# KMO_IO_MV2_3.net
KiCad netlist of a schematic drawn in EAGLE
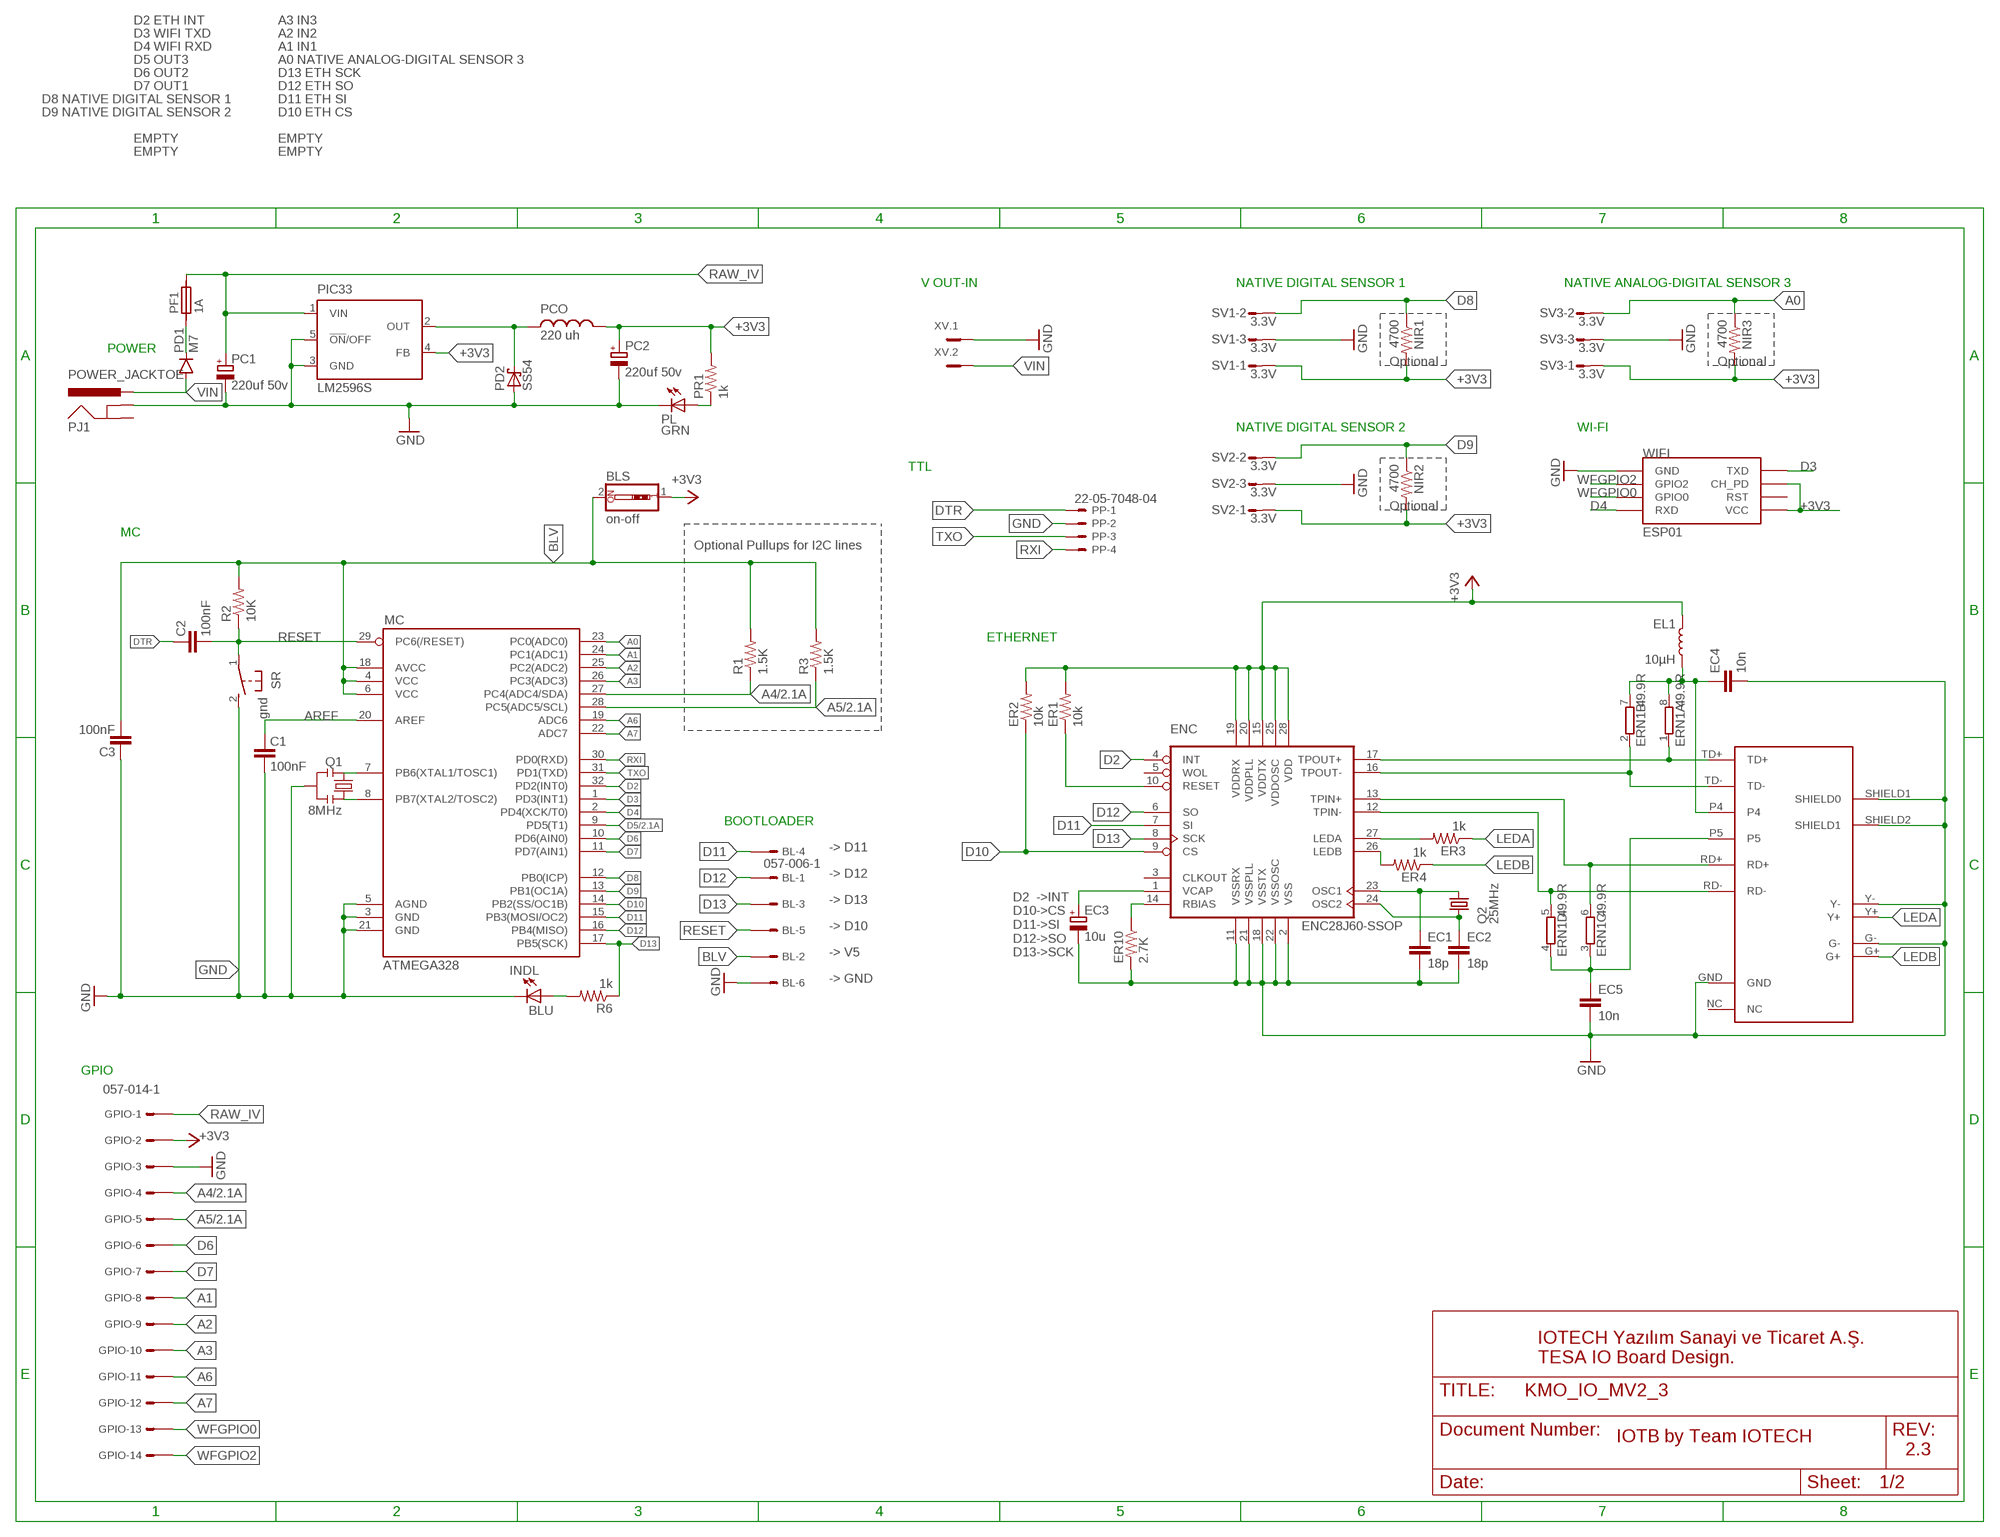
[diagram p0: schematic, sheet 1]
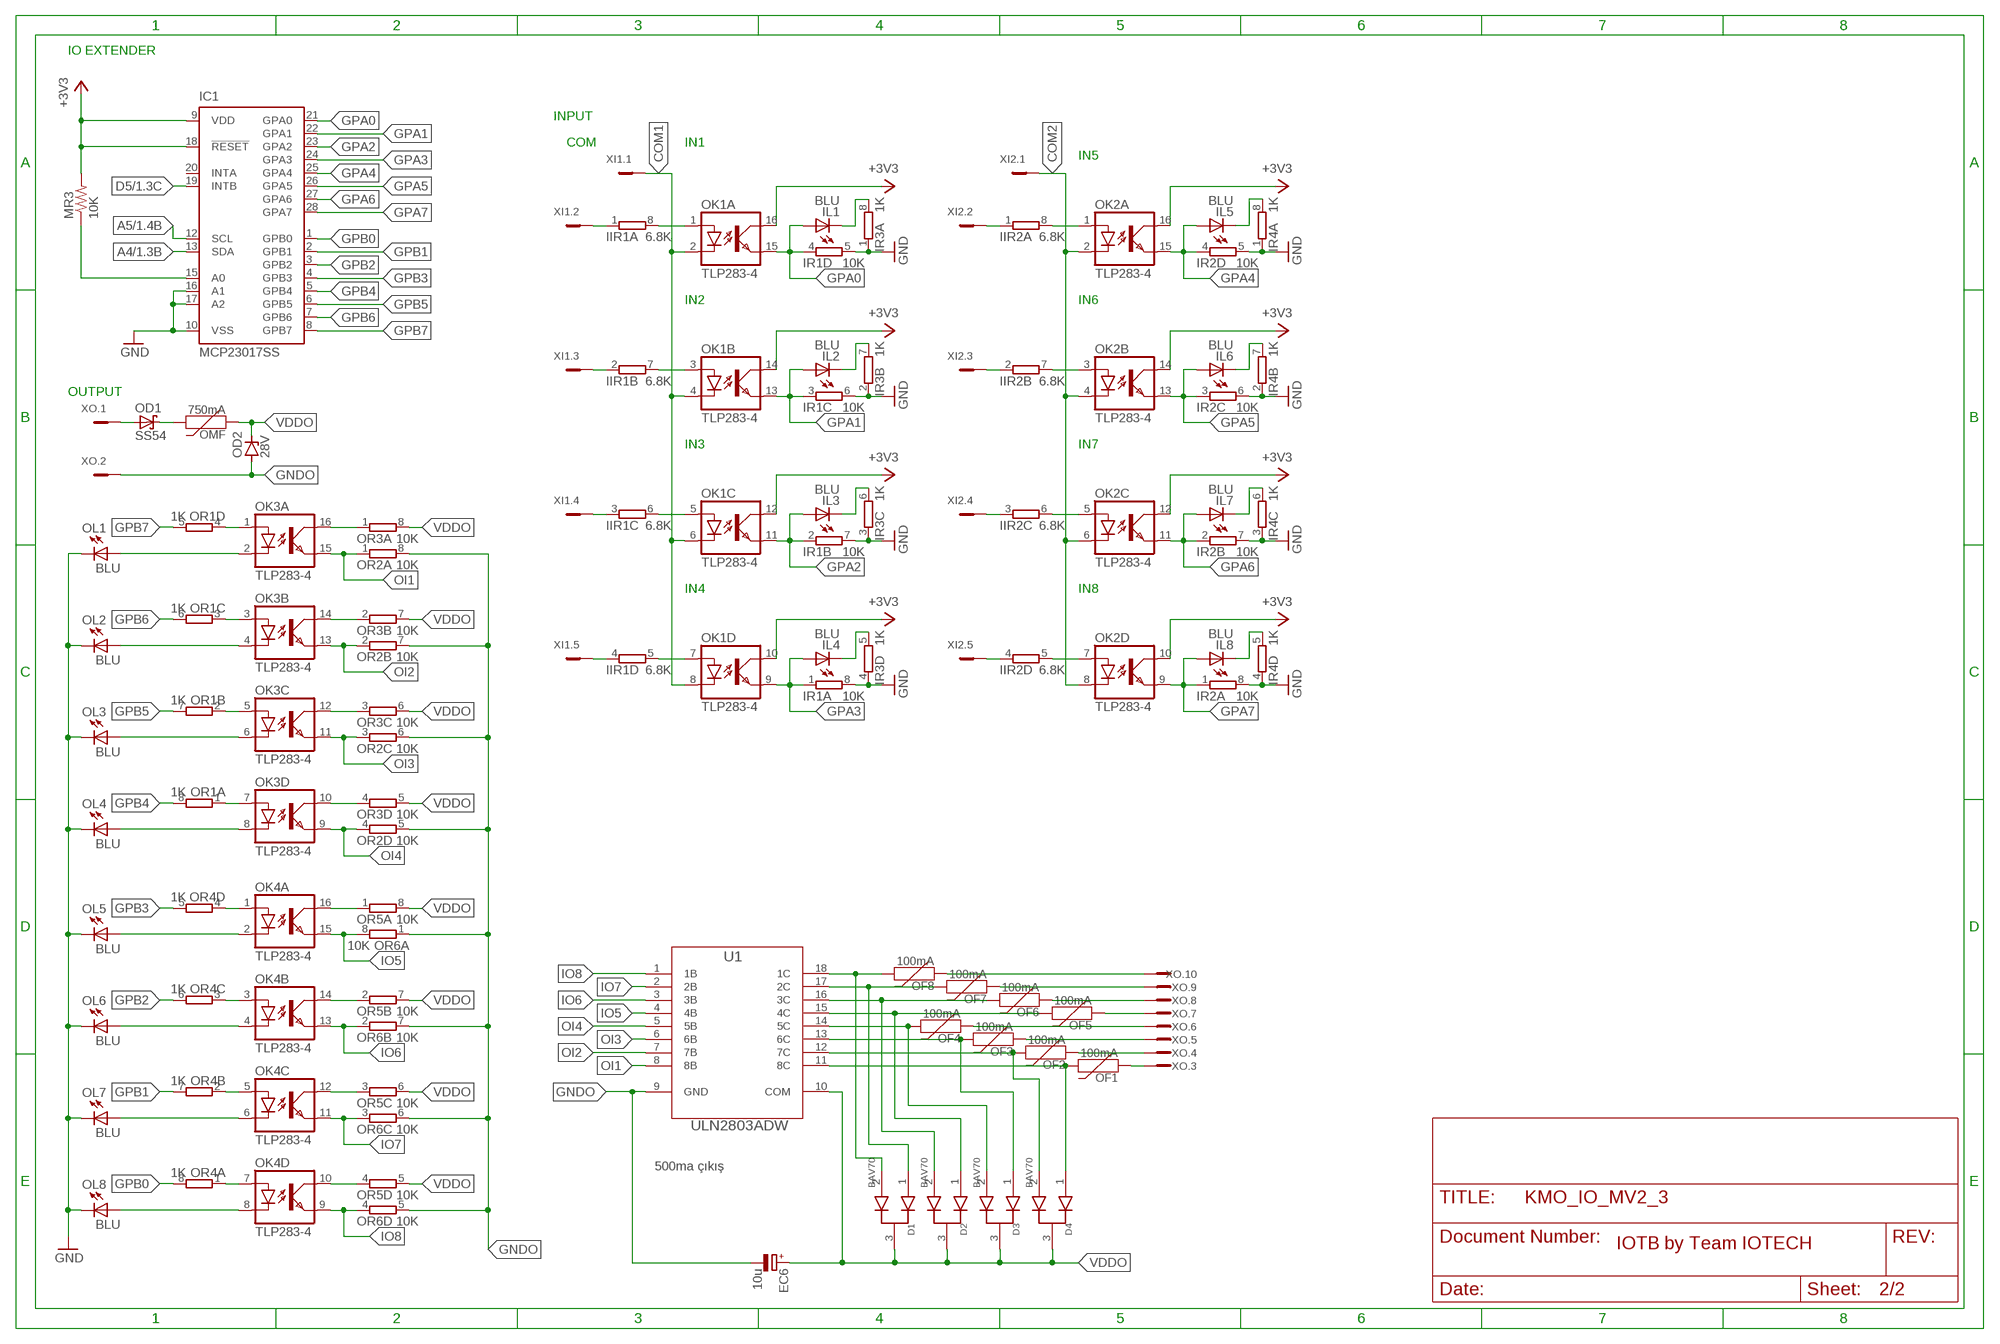
[diagram p1: schematic, sheet 2]

(export (version "E")
  (design (tool "Eeschema 10.0.6"))
  (components
    (comp (ref "D1")
      (value "BAV70")
      (footprint "eagle-import:SOT-23-3")
      (fields (field (name "MF") "Multicomp") (field (name "MP") "BAV70+"))
      (libsource (lib "eagle-import") (part "BAV70"))
    )
    (comp (ref "D2")
      (value "BAV70")
      (footprint "eagle-import:SOT-23-3")
      (fields (field (name "MF") "Multicomp") (field (name "MP") "BAV70+"))
      (libsource (lib "eagle-import") (part "BAV70"))
    )
    (comp (ref "D3")
      (value "BAV70")
      (footprint "eagle-import:SOT-23-3")
      (fields (field (name "MF") "Multicomp") (field (name "MP") "BAV70+"))
      (libsource (lib "eagle-import") (part "BAV70"))
    )
    (comp (ref "D4")
      (value "BAV70")
      (footprint "eagle-import:SOT-23-3")
      (fields (field (name "MF") "Multicomp") (field (name "MP") "BAV70+"))
      (libsource (lib "eagle-import") (part "BAV70"))
    )
    (comp (ref "EC6")
      (value "10u")
      (footprint "eagle-import:CT3216")
      (libsource (lib "eagle-import") (part "CPOL-EUCT3216"))
    )
    (comp (ref "IC1")
      (value "MCP23017SS")
      (footprint "eagle-import:SSOP28")
      (fields (field (name "MF") "MICROCHIP") (field (name "MPN") "MCP23017-E/SS"))
      (libsource (lib "eagle-import") (part "MCP23017SS"))
    )
    (comp (ref "IIR1")
      (value "6.8K")
      (footprint "eagle-import:0603-ARV")
      (libsource (lib "eagle-import") (part "4R-N0603-ARV"))
    )
    (comp (ref "IIR2")
      (value "6.8K")
      (footprint "eagle-import:0603-ARV")
      (libsource (lib "eagle-import") (part "4R-N0603-ARV"))
    )
    (comp (ref "IL1")
      (value "BLU")
      (footprint "eagle-import:CHIP-LED0805")
      (libsource (lib "eagle-import") (part "LEDCHIP-LED0805"))
    )
    (comp (ref "IL2")
      (value "BLU")
      (footprint "eagle-import:CHIP-LED0805")
      (libsource (lib "eagle-import") (part "LEDCHIP-LED0805"))
    )
    (comp (ref "IL3")
      (value "BLU")
      (footprint "eagle-import:CHIP-LED0805")
      (libsource (lib "eagle-import") (part "LEDCHIP-LED0805"))
    )
    (comp (ref "IL4")
      (value "BLU")
      (footprint "eagle-import:CHIP-LED0805")
      (libsource (lib "eagle-import") (part "LEDCHIP-LED0805"))
    )
    (comp (ref "IL5")
      (value "BLU")
      (footprint "eagle-import:CHIP-LED0805")
      (libsource (lib "eagle-import") (part "LEDCHIP-LED0805"))
    )
    (comp (ref "IL6")
      (value "BLU")
      (footprint "eagle-import:CHIP-LED0805")
      (libsource (lib "eagle-import") (part "LEDCHIP-LED0805"))
    )
    (comp (ref "IL7")
      (value "BLU")
      (footprint "eagle-import:CHIP-LED0805")
      (libsource (lib "eagle-import") (part "LEDCHIP-LED0805"))
    )
    (comp (ref "IL8")
      (value "BLU")
      (footprint "eagle-import:CHIP-LED0805")
      (libsource (lib "eagle-import") (part "LEDCHIP-LED0805"))
    )
    (comp (ref "IR1")
      (value "10K")
      (footprint "eagle-import:0603-ARV")
      (libsource (lib "eagle-import") (part "4R-N0603-ARV"))
    )
    (comp (ref "IR2")
      (value "10K")
      (footprint "eagle-import:0603-ARV")
      (libsource (lib "eagle-import") (part "4R-N0603-ARV"))
    )
    (comp (ref "IR3")
      (value "1K")
      (footprint "eagle-import:0603-ARV")
      (libsource (lib "eagle-import") (part "4R-N0603-ARV"))
    )
    (comp (ref "IR4")
      (value "1K")
      (footprint "eagle-import:0603-ARV")
      (libsource (lib "eagle-import") (part "4R-N0603-ARV"))
    )
    (comp (ref "MR3")
      (value "10K")
      (footprint "eagle-import:0805")
      (libsource (lib "eagle-import") (part "RESISTOR0805-RES"))
    )
    (comp (ref "OD1")
      (value "SS54")
      (footprint "eagle-import:SMB")
      (libsource (lib "eagle-import") (part "SCHOTTKY-DIODESMD"))
    )
    (comp (ref "OD2")
      (value "28V")
      (footprint "eagle-import:SMB")
      (libsource (lib "eagle-import") (part "ZENER-DIODESMB"))
    )
    (comp (ref "OF1")
      (value "100mA")
      (footprint "eagle-import:1206")
      (libsource (lib "eagle-import") (part "PPTC_0.75A"))
    )
    (comp (ref "OF2")
      (value "100mA")
      (footprint "eagle-import:1206")
      (libsource (lib "eagle-import") (part "PPTC_0.75A"))
    )
    (comp (ref "OF3")
      (value "100mA")
      (footprint "eagle-import:1206")
      (libsource (lib "eagle-import") (part "PPTC_0.75A"))
    )
    (comp (ref "OF4")
      (value "100mA")
      (footprint "eagle-import:1206")
      (libsource (lib "eagle-import") (part "PPTC_0.75A"))
    )
    (comp (ref "OF5")
      (value "100mA")
      (footprint "eagle-import:1206")
      (libsource (lib "eagle-import") (part "PPTC_0.75A"))
    )
    (comp (ref "OF6")
      (value "100mA")
      (footprint "eagle-import:1206")
      (libsource (lib "eagle-import") (part "PPTC_0.75A"))
    )
    (comp (ref "OF7")
      (value "100mA")
      (footprint "eagle-import:1206")
      (libsource (lib "eagle-import") (part "PPTC_0.75A"))
    )
    (comp (ref "OF8")
      (value "100mA")
      (footprint "eagle-import:1206")
      (libsource (lib "eagle-import") (part "PPTC_0.75A"))
    )
    (comp (ref "OK1")
      (value "TLP283-4")
      (footprint "eagle-import:MINI-FLAT-16")
      (fields (field (name "SPICEPREFIX") "O"))
      (libsource (lib "eagle-import") (part "TLP283-4"))
    )
    (comp (ref "OK2")
      (value "TLP283-4")
      (footprint "eagle-import:MINI-FLAT-16")
      (fields (field (name "SPICEPREFIX") "O"))
      (libsource (lib "eagle-import") (part "TLP283-4"))
    )
    (comp (ref "OK3")
      (value "TLP283-4")
      (footprint "eagle-import:MINI-FLAT-16")
      (libsource (lib "eagle-import") (part "TLP283-4"))
    )
    (comp (ref "OK4")
      (value "TLP283-4")
      (footprint "eagle-import:MINI-FLAT-16")
      (libsource (lib "eagle-import") (part "TLP283-4"))
    )
    (comp (ref "OL1")
      (value "BLU")
      (footprint "eagle-import:CHIP-LED0805")
      (libsource (lib "eagle-import") (part "LEDCHIP-LED0805"))
    )
    (comp (ref "OL2")
      (value "BLU")
      (footprint "eagle-import:CHIP-LED0805")
      (libsource (lib "eagle-import") (part "LEDCHIP-LED0805"))
    )
    (comp (ref "OL3")
      (value "BLU")
      (footprint "eagle-import:CHIP-LED0805")
      (libsource (lib "eagle-import") (part "LEDCHIP-LED0805"))
    )
    (comp (ref "OL4")
      (value "BLU")
      (footprint "eagle-import:CHIP-LED0805")
      (libsource (lib "eagle-import") (part "LEDCHIP-LED0805"))
    )
    (comp (ref "OL5")
      (value "BLU")
      (footprint "eagle-import:CHIP-LED0805")
      (libsource (lib "eagle-import") (part "LEDCHIP-LED0805"))
    )
    (comp (ref "OL6")
      (value "BLU")
      (footprint "eagle-import:CHIP-LED0805")
      (libsource (lib "eagle-import") (part "LEDCHIP-LED0805"))
    )
    (comp (ref "OL7")
      (value "BLU")
      (footprint "eagle-import:CHIP-LED0805")
      (libsource (lib "eagle-import") (part "LEDCHIP-LED0805"))
    )
    (comp (ref "OL8")
      (value "BLU")
      (footprint "eagle-import:CHIP-LED0805")
      (libsource (lib "eagle-import") (part "LEDCHIP-LED0805"))
    )
    (comp (ref "OMF")
      (value "750mA")
      (footprint "eagle-import:1206")
      (libsource (lib "eagle-import") (part "PPTC_0.75A"))
    )
    (comp (ref "OR1")
      (value "1K")
      (footprint "eagle-import:0603-ARV")
      (libsource (lib "eagle-import") (part "4R-N0603-ARV"))
    )
    (comp (ref "OR2")
      (value "10K")
      (footprint "eagle-import:0603-ARV")
      (libsource (lib "eagle-import") (part "4R-N0603-ARV"))
    )
    (comp (ref "OR3")
      (value "10K")
      (footprint "eagle-import:0603-ARV")
      (libsource (lib "eagle-import") (part "4R-N0603-ARV"))
    )
    (comp (ref "OR4")
      (value "1K")
      (footprint "eagle-import:0603-ARV")
      (libsource (lib "eagle-import") (part "4R-N0603-ARV"))
    )
    (comp (ref "OR5")
      (value "10K")
      (footprint "eagle-import:0603-ARV")
      (libsource (lib "eagle-import") (part "4R-N0603-ARV"))
    )
    (comp (ref "OR6")
      (value "10K")
      (footprint "eagle-import:0603-ARV")
      (libsource (lib "eagle-import") (part "4R-N0603-ARV"))
    )
    (comp (ref "U1")
      (value "ULN2803ADW")
      (footprint "eagle-import:SOIC127P1030X265-18N")
      (libsource (lib "eagle-import") (part "ULN2803ADW"))
    )
    (comp (ref "XI1")
      (value "MC5")
      (footprint "eagle-import:MC5")
      (libsource (lib "eagle-import") (part "MC5"))
    )
    (comp (ref "XI2")
      (value "MC5")
      (footprint "eagle-import:MC5")
      (libsource (lib "eagle-import") (part "MC5"))
    )
    (comp (ref "XO")
      (value "MC10")
      (footprint "eagle-import:MC10")
      (libsource (lib "eagle-import") (part "MC10"))
    )
    (comp (ref "BL")
      (value "057-006-1")
      (footprint "eagle-import:057-006-1")
      (libsource (lib "eagle-import") (part "057-006-1"))
    )
    (comp (ref "BLS")
      (value "on-off")
      (footprint "eagle-import:EDG-01")
      (libsource (lib "eagle-import") (part "SW_DIP-1"))
    )
    (comp (ref "C1")
      (value "100nF")
      (footprint "eagle-import:0805")
      (libsource (lib "eagle-import") (part "CAP0805"))
    )
    (comp (ref "C2")
      (value "100nF")
      (footprint "eagle-import:0805")
      (libsource (lib "eagle-import") (part "CAP0805"))
    )
    (comp (ref "C3")
      (value "100nF")
      (footprint "eagle-import:0805")
      (libsource (lib "eagle-import") (part "CAP0805"))
    )
    (comp (ref "EC1")
      (value "18p")
      (footprint "eagle-import:0805")
      (libsource (lib "eagle-import") (part "CAP0805"))
    )
    (comp (ref "EC2")
      (value "18p")
      (footprint "eagle-import:0805")
      (libsource (lib "eagle-import") (part "CAP0805"))
    )
    (comp (ref "EC3")
      (value "10u")
      (footprint "eagle-import:CT3216")
      (libsource (lib "eagle-import") (part "CPOL-EUCT3216"))
    )
    (comp (ref "EC4")
      (value "10n")
      (footprint "eagle-import:0805")
      (libsource (lib "eagle-import") (part "CAP0805"))
    )
    (comp (ref "EC5")
      (value "10n")
      (footprint "eagle-import:0805")
      (libsource (lib "eagle-import") (part "CAP0805"))
    )
    (comp (ref "EL1")
      (value "10µH")
      (footprint "eagle-import:0805")
      (libsource (lib "eagle-import") (part "INDUCTOR-0805-3.3UH"))
    )
    (comp (ref "ENC")
      (value "ENC28J60-SSOP")
      (footprint "eagle-import:SSOP28")
      (libsource (lib "eagle-import") (part "ENC28J60-SSOP"))
    )
    (comp (ref "ER1")
      (value "10k")
      (footprint "eagle-import:0805")
      (libsource (lib "eagle-import") (part "RESISTOR0805-RES"))
    )
    (comp (ref "ER2")
      (value "10k")
      (footprint "eagle-import:0805")
      (libsource (lib "eagle-import") (part "RESISTOR0805-RES"))
    )
    (comp (ref "ER3")
      (value "1k")
      (footprint "eagle-import:0805")
      (libsource (lib "eagle-import") (part "RESISTOR0805-RES"))
    )
    (comp (ref "ER4")
      (value "1k")
      (footprint "eagle-import:0805")
      (libsource (lib "eagle-import") (part "RESISTOR0805-RES"))
    )
    (comp (ref "ER10")
      (value "2.7K")
      (footprint "eagle-import:0805")
      (libsource (lib "eagle-import") (part "RESISTOR0805-RES"))
    )
    (comp (ref "ERN1")
      (value "49.9R")
      (footprint "eagle-import:0603-ARV")
      (libsource (lib "eagle-import") (part "4R-N0603-ARV"))
    )
    (comp (ref "GPIO")
      (value "057-014-1")
      (footprint "eagle-import:057-014-1")
      (libsource (lib "eagle-import") (part "057-014-1"))
    )
    (comp (ref "INDL")
      (value "BLU")
      (footprint "eagle-import:CHIP-LED0805")
      (libsource (lib "eagle-import") (part "LEDCHIP-LED0805"))
    )
    (comp (ref "MC")
      (value "ATMEGA328")
      (footprint "eagle-import:TQFP32-08")
      (libsource (lib "eagle-import") (part "ATMEGA168"))
    )
    (comp (ref "NIR1")
      (value "4700")
      (footprint "eagle-import:0805")
      (libsource (lib "eagle-import") (part "RESISTOR0805-RES"))
    )
    (comp (ref "NIR2")
      (value "4700")
      (footprint "eagle-import:0805")
      (libsource (lib "eagle-import") (part "RESISTOR0805-RES"))
    )
    (comp (ref "NIR3")
      (value "4700")
      (footprint "eagle-import:0805")
      (libsource (lib "eagle-import") (part "RESISTOR0805-RES"))
    )
    (comp (ref "PC1")
      (value "220uf 50v")
      (footprint "eagle-import:140CLH-1010")
      (libsource (lib "eagle-import") (part "CPOL-EU140CLH-1010"))
    )
    (comp (ref "PC2")
      (value "220uf 50v")
      (footprint "eagle-import:140CLH-1010")
      (libsource (lib "eagle-import") (part "CPOL-EU140CLH-1010"))
    )
    (comp (ref "PCO")
      (value "220 uh")
      (footprint "eagle-import:MSS1260")
      (libsource (lib "eagle-import") (part "MSS1260"))
    )
    (comp (ref "PD1")
      (value "M7")
      (footprint "eagle-import:SMA-DIODE")
      (libsource (lib "eagle-import") (part "DIODESMA"))
    )
    (comp (ref "PD2")
      (value "SS54")
      (footprint "eagle-import:SMB")
      (libsource (lib "eagle-import") (part "SCHOTTKY-DIODESMD"))
    )
    (comp (ref "PF1")
      (value "1A")
      (footprint "eagle-import:1820")
      (libsource (lib "eagle-import") (part "SIBA194600"))
    )
    (comp (ref "PIC33")
      (value "LM2596S")
      (footprint "eagle-import:TO263-5")
      (fields (field (name "MF") "NATIONAL SEMICONDUCTOR") (field (name "MPN") "LM2596S-ADJ/NOPB"))
      (libsource (lib "eagle-import") (part "LM2596S"))
    )
    (comp (ref "PJ1")
      (value "POWER_JACKTOE")
      (footprint "eagle-import:POWER_JACK_SMD_OVERPASTE_TOE")
      (libsource (lib "eagle-import") (part "POWER_JACKTOE"))
    )
    (comp (ref "PL")
      (value "GRN")
      (footprint "eagle-import:CHIP-LED0805")
      (libsource (lib "eagle-import") (part "LEDCHIP-LED0805"))
    )
    (comp (ref "PP")
      (value "22-05-7048-04")
      (footprint "eagle-import:7395-04")
      (fields (field (name "MF") "MOLEX"))
      (libsource (lib "eagle-import") (part "22-?-0405-7048"))
    )
    (comp (ref "PR1")
      (value "1k")
      (footprint "eagle-import:0805")
      (libsource (lib "eagle-import") (part "RESISTOR0805-RES"))
    )
    (comp (ref "Q1")
      (value "8MHz")
      (footprint "eagle-import:RESONATOR-SMD-1_1")
      (libsource (lib "eagle-import") (part "RESONATOR1{colon}1"))
    )
    (comp (ref "Q2")
      (value "25MHz")
      (footprint "eagle-import:5.0X3.2_2")
      (libsource (lib "eagle-import") (part "KX-9B"))
    )
    (comp (ref "R1")
      (value "1.5K")
      (footprint "eagle-import:0805")
      (libsource (lib "eagle-import") (part "RESISTOR0805-RES"))
    )
    (comp (ref "R2")
      (value "10K")
      (footprint "eagle-import:0805")
      (libsource (lib "eagle-import") (part "RESISTOR0805-RES"))
    )
    (comp (ref "R3")
      (value "1.5K")
      (footprint "eagle-import:0805")
      (libsource (lib "eagle-import") (part "RESISTOR0805-RES"))
    )
    (comp (ref "R6")
      (value "1k")
      (footprint "eagle-import:0805")
      (libsource (lib "eagle-import") (part "RESISTOR0805-RES"))
    )
    (comp (ref "SR")
      (value "gnd")
      (footprint "eagle-import:B3F-31XX")
      (fields (field (name "MPN") "B3F-3100"))
      (libsource (lib "eagle-import") (part "31-XX"))
    )
    (comp (ref "SV1")
      (value "3.3V")
      (footprint "eagle-import:S03P")
      (libsource (lib "eagle-import") (part "S03P"))
    )
    (comp (ref "SV2")
      (value "3.3V")
      (footprint "eagle-import:S03P")
      (libsource (lib "eagle-import") (part "S03P"))
    )
    (comp (ref "SV3")
      (value "3.3V")
      (footprint "eagle-import:S03P")
      (libsource (lib "eagle-import") (part "S03P"))
    )
    (comp (ref "U$2")
      (value "HR911105A")
      (footprint "eagle-import:RJ45")
      (libsource (lib "eagle-import") (part "HR911105A"))
    )
    (comp (ref "WIFI")
      (value "ESP01")
      (footprint "eagle-import:ESP01")
      (libsource (lib "eagle-import") (part "ESP01"))
    )
    (comp (ref "XV")
      (value "MC2")
      (footprint "eagle-import:MC2")
      (libsource (lib "eagle-import") (part "MC2"))
    )
  )
  (nets
    (net (code "1") (name "+3V3") (class "Default")
      (node (ref "BLS") (pin "1") (pinfunction "1_1") (pintype "passive"))
      (node (ref "EL1") (pin "1") (pinfunction "1_1") (pintype "passive"))
      (node (ref "ENC") (pin "15") (pinfunction "VDDTX_15") (pintype "power_in"))
      (node (ref "ENC") (pin "19") (pinfunction "VDDRX_19") (pintype "power_in"))
      (node (ref "ENC") (pin "20") (pinfunction "VDDPLL_20") (pintype "power_in"))
      (node (ref "ENC") (pin "25") (pinfunction "VDDOSC_25") (pintype "power_in"))
      (node (ref "ENC") (pin "28") (pinfunction "VDD_28") (pintype "power_in"))
      (node (ref "ER1") (pin "2") (pinfunction "2_2") (pintype "passive"))
      (node (ref "ER2") (pin "2") (pinfunction "2_2") (pintype "passive"))
      (node (ref "GPIO") (pin "2") (pinfunction "S_2") (pintype "passive"))
      (node (ref "IC1") (pin "18") (pinfunction "~{RESET}_18") (pintype "input"))
      (node (ref "IC1") (pin "9") (pinfunction "VDD_9") (pintype "power_in"))
      (node (ref "MR3") (pin "2") (pinfunction "2_2") (pintype "passive"))
      (node (ref "NIR1") (pin "2") (pinfunction "2_2") (pintype "passive"))
      (node (ref "NIR2") (pin "2") (pinfunction "2_2") (pintype "passive"))
      (node (ref "NIR3") (pin "2") (pinfunction "2_2") (pintype "passive"))
      (node (ref "OK1") (pin "10") (pinfunction "COL_10") (pintype "passive"))
      (node (ref "OK1") (pin "12") (pinfunction "COL_12") (pintype "passive"))
      (node (ref "OK1") (pin "14") (pinfunction "COL_14") (pintype "passive"))
      (node (ref "OK1") (pin "16") (pinfunction "COL_16") (pintype "passive"))
      (node (ref "OK2") (pin "10") (pinfunction "COL_10") (pintype "passive"))
      (node (ref "OK2") (pin "12") (pinfunction "COL_12") (pintype "passive"))
      (node (ref "OK2") (pin "14") (pinfunction "COL_14") (pintype "passive"))
      (node (ref "OK2") (pin "16") (pinfunction "COL_16") (pintype "passive"))
      (node (ref "PC2") (pin "+") (pinfunction "+_+") (pintype "passive"))
      (node (ref "PCO") (pin "P$1") (pinfunction "P$1_P$1") (pintype "passive"))
      (node (ref "PIC33") (pin "4") (pinfunction "FB_4") (pintype "input"))
      (node (ref "PR1") (pin "2") (pinfunction "2_2") (pintype "passive"))
      (node (ref "SV1") (pin "1") (pinfunction "S_1") (pintype "passive"))
      (node (ref "SV2") (pin "1") (pinfunction "S_1") (pintype "passive"))
      (node (ref "SV3") (pin "1") (pinfunction "S_1") (pintype "passive"))
      (node (ref "WIFI") (pin "CH_PD") (pinfunction "CH_PD_CH_PD") (pintype "bidirectional"))
      (node (ref "WIFI") (pin "VCC") (pinfunction "VCC_VCC") (pintype "bidirectional"))
    )
    (net (code "2") (name "A0") (class "Default")
      (node (ref "MC") (pin "23") (pinfunction "PC0(ADC0)_23") (pintype "bidirectional"))
      (node (ref "NIR3") (pin "1") (pinfunction "1_1") (pintype "passive"))
      (node (ref "SV3") (pin "2") (pinfunction "S_2") (pintype "passive"))
    )
    (net (code "3") (name "A1") (class "Default")
      (node (ref "GPIO") (pin "8") (pinfunction "S_8") (pintype "passive"))
      (node (ref "MC") (pin "24") (pinfunction "PC1(ADC1)_24") (pintype "bidirectional"))
    )
    (net (code "4") (name "A2") (class "Default")
      (node (ref "GPIO") (pin "9") (pinfunction "S_9") (pintype "passive"))
      (node (ref "MC") (pin "25") (pinfunction "PC2(ADC2)_25") (pintype "bidirectional"))
    )
    (net (code "5") (name "A3") (class "Default")
      (node (ref "GPIO") (pin "10") (pinfunction "S_10") (pintype "passive"))
      (node (ref "MC") (pin "26") (pinfunction "PC3(ADC3)_26") (pintype "bidirectional"))
    )
    (net (code "6") (name "A4") (class "Default")
      (node (ref "GPIO") (pin "4") (pinfunction "S_4") (pintype "passive"))
      (node (ref "IC1") (pin "13") (pinfunction "SDA_13") (pintype "bidirectional"))
      (node (ref "MC") (pin "27") (pinfunction "PC4(ADC4/SDA)_27") (pintype "bidirectional"))
      (node (ref "R1") (pin "1") (pinfunction "1_1") (pintype "passive"))
    )
    (net (code "7") (name "A5") (class "Default")
      (node (ref "GPIO") (pin "5") (pinfunction "S_5") (pintype "passive"))
      (node (ref "IC1") (pin "12") (pinfunction "SCL_12") (pintype "input"))
      (node (ref "MC") (pin "28") (pinfunction "PC5(ADC5/SCL)_28") (pintype "bidirectional"))
      (node (ref "R3") (pin "1") (pinfunction "1_1") (pintype "passive"))
    )
    (net (code "8") (name "A6") (class "Default")
      (node (ref "GPIO") (pin "11") (pinfunction "S_11") (pintype "passive"))
      (node (ref "MC") (pin "19") (pinfunction "ADC6_19") (pintype "bidirectional"))
    )
    (net (code "9") (name "A7") (class "Default")
      (node (ref "GPIO") (pin "12") (pinfunction "S_12") (pintype "passive"))
      (node (ref "MC") (pin "22") (pinfunction "ADC7_22") (pintype "bidirectional"))
    )
    (net (code "10") (name "AREF") (class "Default")
      (node (ref "C1") (pin "2") (pinfunction "2_2") (pintype "passive"))
      (node (ref "MC") (pin "20") (pinfunction "AREF_20") (pintype "bidirectional"))
    )
    (net (code "11") (name "BLV") (class "Default")
      (node (ref "BL") (pin "2") (pinfunction "S_2") (pintype "passive"))
      (node (ref "BLS") (pin "2") (pinfunction "2_2") (pintype "passive"))
      (node (ref "C3") (pin "1") (pinfunction "1_1") (pintype "passive"))
      (node (ref "MC") (pin "18") (pinfunction "AVCC_18") (pintype "bidirectional"))
      (node (ref "MC") (pin "4") (pinfunction "VCC_4") (pintype "bidirectional"))
      (node (ref "MC") (pin "6") (pinfunction "VCC_6") (pintype "bidirectional"))
      (node (ref "R1") (pin "2") (pinfunction "2_2") (pintype "passive"))
      (node (ref "R2") (pin "2") (pinfunction "2_2") (pintype "passive"))
      (node (ref "R3") (pin "2") (pinfunction "2_2") (pintype "passive"))
    )
    (net (code "12") (name "COM1") (class "Default")
      (node (ref "OK1") (pin "2") (pinfunction "C_2") (pintype "passive"))
      (node (ref "OK1") (pin "4") (pinfunction "C_4") (pintype "passive"))
      (node (ref "OK1") (pin "6") (pinfunction "C_6") (pintype "passive"))
      (node (ref "OK1") (pin "8") (pinfunction "C_8") (pintype "passive"))
      (node (ref "XI1") (pin "1") (pinfunction "SK_1") (pintype "passive"))
    )
    (net (code "13") (name "COM2") (class "Default")
      (node (ref "OK2") (pin "2") (pinfunction "C_2") (pintype "passive"))
      (node (ref "OK2") (pin "4") (pinfunction "C_4") (pintype "passive"))
      (node (ref "OK2") (pin "6") (pinfunction "C_6") (pintype "passive"))
      (node (ref "OK2") (pin "8") (pinfunction "C_8") (pintype "passive"))
      (node (ref "XI2") (pin "1") (pinfunction "SK_1") (pintype "passive"))
    )
    (net (code "14") (name "D2") (class "Default")
      (node (ref "ENC") (pin "4") (pinfunction "INT_4") (pintype "output"))
      (node (ref "MC") (pin "32") (pinfunction "PD2(INT0)_32") (pintype "bidirectional"))
    )
    (net (code "15") (name "D3") (class "Default")
      (node (ref "MC") (pin "1") (pinfunction "PD3(INT1)_1") (pintype "bidirectional"))
      (node (ref "WIFI") (pin "TX") (pinfunction "TXD_TX") (pintype "bidirectional"))
    )
    (net (code "16") (name "D4") (class "Default")
      (node (ref "MC") (pin "2") (pinfunction "PD4(XCK/T0)_2") (pintype "bidirectional"))
      (node (ref "WIFI") (pin "RX") (pinfunction "RXD_RX") (pintype "bidirectional"))
    )
    (net (code "17") (name "D5") (class "Default")
      (node (ref "IC1") (pin "19") (pinfunction "INTB_19") (pintype "output"))
      (node (ref "MC") (pin "9") (pinfunction "PD5(T1)_9") (pintype "bidirectional"))
    )
    (net (code "18") (name "D6") (class "Default")
      (node (ref "GPIO") (pin "6") (pinfunction "S_6") (pintype "passive"))
      (node (ref "MC") (pin "10") (pinfunction "PD6(AIN0)_10") (pintype "bidirectional"))
    )
    (net (code "19") (name "D7") (class "Default")
      (node (ref "GPIO") (pin "7") (pinfunction "S_7") (pintype "passive"))
      (node (ref "MC") (pin "11") (pinfunction "PD7(AIN1)_11") (pintype "bidirectional"))
    )
    (net (code "20") (name "D8") (class "Default")
      (node (ref "MC") (pin "12") (pinfunction "PB0(ICP)_12") (pintype "bidirectional"))
      (node (ref "NIR1") (pin "1") (pinfunction "1_1") (pintype "passive"))
      (node (ref "SV1") (pin "2") (pinfunction "S_2") (pintype "passive"))
    )
    (net (code "21") (name "D9") (class "Default")
      (node (ref "MC") (pin "13") (pinfunction "PB1(OC1A)_13") (pintype "bidirectional"))
      (node (ref "NIR2") (pin "1") (pinfunction "1_1") (pintype "passive"))
      (node (ref "SV2") (pin "2") (pinfunction "S_2") (pintype "passive"))
    )
    (net (code "22") (name "D10") (class "Default")
      (node (ref "ENC") (pin "9") (pinfunction "CS_9") (pintype "input"))
      (node (ref "ER2") (pin "1") (pinfunction "1_1") (pintype "passive"))
      (node (ref "MC") (pin "14") (pinfunction "PB2(SS/OC1B)_14") (pintype "bidirectional"))
    )
    (net (code "23") (name "D11") (class "Default")
      (node (ref "BL") (pin "4") (pinfunction "S_4") (pintype "passive"))
      (node (ref "ENC") (pin "7") (pinfunction "SI_7") (pintype "input"))
      (node (ref "MC") (pin "15") (pinfunction "PB3(MOSI/OC2)_15") (pintype "bidirectional"))
    )
    (net (code "24") (name "D12") (class "Default")
      (node (ref "BL") (pin "1") (pinfunction "S_1") (pintype "passive"))
      (node (ref "ENC") (pin "6") (pinfunction "SO_6") (pintype "output"))
      (node (ref "MC") (pin "16") (pinfunction "PB4(MISO)_16") (pintype "bidirectional"))
    )
    (net (code "25") (name "D13") (class "Default")
      (node (ref "BL") (pin "3") (pinfunction "S_3") (pintype "passive"))
      (node (ref "ENC") (pin "8") (pinfunction "SCK_8") (pintype "input"))
      (node (ref "MC") (pin "17") (pinfunction "PB5(SCK)_17") (pintype "bidirectional"))
      (node (ref "R6") (pin "1") (pinfunction "1_1") (pintype "passive"))
    )
    (net (code "26") (name "DTR") (class "Default")
      (node (ref "C2") (pin "2") (pinfunction "2_2") (pintype "passive"))
      (node (ref "PP") (pin "1") (pinfunction "S_1") (pintype "passive"))
    )
    (net (code "27") (name "GND") (class "Default")
      (node (ref "BL") (pin "6") (pinfunction "S_6") (pintype "passive"))
      (node (ref "C1") (pin "1") (pinfunction "1_1") (pintype "passive"))
      (node (ref "C3") (pin "2") (pinfunction "2_2") (pintype "passive"))
      (node (ref "EC1") (pin "2") (pinfunction "2_2") (pintype "passive"))
      (node (ref "EC2") (pin "2") (pinfunction "2_2") (pintype "passive"))
      (node (ref "EC3") (pin "-") (pinfunction "-_-") (pintype "passive"))
      (node (ref "EC4") (pin "2") (pinfunction "2_2") (pintype "passive"))
      (node (ref "EC5") (pin "2") (pinfunction "2_2") (pintype "passive"))
      (node (ref "ENC") (pin "11") (pinfunction "VSSRX_11") (pintype "power_in"))
      (node (ref "ENC") (pin "18") (pinfunction "VSSTX_18") (pintype "power_in"))
      (node (ref "ENC") (pin "2") (pinfunction "VSS_2") (pintype "power_in"))
      (node (ref "ENC") (pin "21") (pinfunction "VSSPLL_21") (pintype "power_in"))
      (node (ref "ENC") (pin "22") (pinfunction "VSSOSC_22") (pintype "power_in"))
      (node (ref "ER10") (pin "2") (pinfunction "2_2") (pintype "passive"))
      (node (ref "GPIO") (pin "3") (pinfunction "S_3") (pintype "passive"))
      (node (ref "IC1") (pin "10") (pinfunction "VSS_10") (pintype "power_in"))
      (node (ref "IC1") (pin "16") (pinfunction "A1_16") (pintype "input"))
      (node (ref "IC1") (pin "17") (pinfunction "A2_17") (pintype "input"))
      (node (ref "INDL") (pin "C") (pinfunction "C_C") (pintype "passive"))
      (node (ref "IR1") (pin "5") (pinfunction "2_5") (pintype "passive"))
      (node (ref "IR1") (pin "6") (pinfunction "2_6") (pintype "passive"))
      (node (ref "IR1") (pin "7") (pinfunction "2_7") (pintype "passive"))
      (node (ref "IR1") (pin "8") (pinfunction "2_8") (pintype "passive"))
      (node (ref "IR2") (pin "5") (pinfunction "2_5") (pintype "passive"))
      (node (ref "IR2") (pin "6") (pinfunction "2_6") (pintype "passive"))
      (node (ref "IR2") (pin "7") (pinfunction "2_7") (pintype "passive"))
      (node (ref "IR2") (pin "8") (pinfunction "2_8") (pintype "passive"))
      (node (ref "IR3") (pin "1") (pinfunction "1_1") (pintype "passive"))
      (node (ref "IR3") (pin "2") (pinfunction "1_2") (pintype "passive"))
      (node (ref "IR3") (pin "3") (pinfunction "1_3") (pintype "passive"))
      (node (ref "IR3") (pin "4") (pinfunction "1_4") (pintype "passive"))
      (node (ref "IR4") (pin "1") (pinfunction "1_1") (pintype "passive"))
      (node (ref "IR4") (pin "2") (pinfunction "1_2") (pintype "passive"))
      (node (ref "IR4") (pin "3") (pinfunction "1_3") (pintype "passive"))
      (node (ref "IR4") (pin "4") (pinfunction "1_4") (pintype "passive"))
      (node (ref "MC") (pin "21") (pinfunction "GND_21") (pintype "bidirectional"))
      (node (ref "MC") (pin "3") (pinfunction "GND_3") (pintype "bidirectional"))
      (node (ref "MC") (pin "5") (pinfunction "AGND_5") (pintype "bidirectional"))
      (node (ref "OL1") (pin "C") (pinfunction "C_C") (pintype "passive"))
      (node (ref "OL2") (pin "C") (pinfunction "C_C") (pintype "passive"))
      (node (ref "OL3") (pin "C") (pinfunction "C_C") (pintype "passive"))
      (node (ref "OL4") (pin "C") (pinfunction "C_C") (pintype "passive"))
      (node (ref "OL5") (pin "C") (pinfunction "C_C") (pintype "passive"))
      (node (ref "OL6") (pin "C") (pinfunction "C_C") (pintype "passive"))
      (node (ref "OL7") (pin "C") (pinfunction "C_C") (pintype "passive"))
      (node (ref "OL8") (pin "C") (pinfunction "C_C") (pintype "passive"))
      (node (ref "PC1") (pin "-") (pinfunction "-_-") (pintype "passive"))
      (node (ref "PC2") (pin "-") (pinfunction "-_-") (pintype "passive"))
      (node (ref "PD2") (pin "A") (pinfunction "A_A") (pintype "passive"))
      (node (ref "PIC33") (pin "3") (pinfunction "GND_3") (pintype "power_in"))
      (node (ref "PIC33") (pin "5") (pinfunction "~{ON}/OFF_5") (pintype "input"))
      (node (ref "PJ1") (pin "GND") (pinfunction "GNDBREAK_GND") (pintype "bidirectional"))
      (node (ref "PL") (pin "C") (pinfunction "C_C") (pintype "passive"))
      (node (ref "PP") (pin "2") (pinfunction "S_2") (pintype "passive"))
      (node (ref "Q1") (pin "2") (pinfunction "2_2") (pintype "passive"))
      (node (ref "SR") (pin "2") (pinfunction "S_2") (pintype "passive"))
      (node (ref "SV1") (pin "3") (pinfunction "S_3") (pintype "passive"))
      (node (ref "SV2") (pin "3") (pinfunction "S_3") (pintype "passive"))
      (node (ref "SV3") (pin "3") (pinfunction "S_3") (pintype "passive"))
      (node (ref "U$2") (pin "G-") (pinfunction "G-_G-") (pintype "bidirectional"))
      (node (ref "U$2") (pin "GND") (pinfunction "GND_GND") (pintype "bidirectional"))
      (node (ref "U$2") (pin "SHIELD1") (pinfunction "SHIELD0_SHIELD1") (pintype "bidirectional"))
      (node (ref "U$2") (pin "SHIELD2") (pinfunction "SHIELD1_SHIELD2") (pintype "bidirectional"))
      (node (ref "U$2") (pin "Y-") (pinfunction "Y-_Y-") (pintype "bidirectional"))
      (node (ref "WIFI") (pin "GND") (pinfunction "GND_GND") (pintype "bidirectional"))
      (node (ref "XV") (pin "1") (pinfunction "SK_1") (pintype "passive"))
    )
    (net (code "28") (name "GNDO") (class "Default")
      (node (ref "EC6") (pin "-") (pinfunction "-_-") (pintype "passive"))
      (node (ref "OD2") (pin "A") (pinfunction "A_A") (pintype "passive"))
      (node (ref "OR2") (pin "5") (pinfunction "2_5") (pintype "passive"))
      (node (ref "OR2") (pin "6") (pinfunction "2_6") (pintype "passive"))
      (node (ref "OR2") (pin "7") (pinfunction "2_7") (pintype "passive"))
      (node (ref "OR2") (pin "8") (pinfunction "2_8") (pintype "passive"))
      (node (ref "OR6") (pin "1") (pinfunction "1_1") (pintype "passive"))
      (node (ref "OR6") (pin "5") (pinfunction "2_5") (pintype "passive"))
      (node (ref "OR6") (pin "6") (pinfunction "2_6") (pintype "passive"))
      (node (ref "OR6") (pin "7") (pinfunction "2_7") (pintype "passive"))
      (node (ref "U1") (pin "9") (pinfunction "GND_9") (pintype "passive"))
      (node (ref "XO") (pin "2") (pinfunction "SK_2") (pintype "passive"))
    )
    (net (code "29") (name "GPA0") (class "Default")
      (node (ref "IC1") (pin "21") (pinfunction "GPA0_21") (pintype "bidirectional"))
      (node (ref "IL1") (pin "A") (pinfunction "A_A") (pintype "passive"))
      (node (ref "IR1") (pin "4") (pinfunction "1_4") (pintype "passive"))
      (node (ref "OK1") (pin "15") (pinfunction "EMIT_15") (pintype "passive"))
    )
    (net (code "30") (name "GPA1") (class "Default")
      (node (ref "IC1") (pin "22") (pinfunction "GPA1_22") (pintype "bidirectional"))
      (node (ref "IL2") (pin "A") (pinfunction "A_A") (pintype "passive"))
      (node (ref "IR1") (pin "3") (pinfunction "1_3") (pintype "passive"))
      (node (ref "OK1") (pin "13") (pinfunction "EMIT_13") (pintype "passive"))
    )
    (net (code "31") (name "GPA2") (class "Default")
      (node (ref "IC1") (pin "23") (pinfunction "GPA2_23") (pintype "bidirectional"))
      (node (ref "IL3") (pin "A") (pinfunction "A_A") (pintype "passive"))
      (node (ref "IR1") (pin "2") (pinfunction "1_2") (pintype "passive"))
      (node (ref "OK1") (pin "11") (pinfunction "EMIT_11") (pintype "passive"))
    )
    (net (code "32") (name "GPA3") (class "Default")
      (node (ref "IC1") (pin "24") (pinfunction "GPA3_24") (pintype "bidirectional"))
      (node (ref "IL4") (pin "A") (pinfunction "A_A") (pintype "passive"))
      (node (ref "IR1") (pin "1") (pinfunction "1_1") (pintype "passive"))
      (node (ref "OK1") (pin "9") (pinfunction "EMIT_9") (pintype "passive"))
    )
    (net (code "33") (name "GPA4") (class "Default")
      (node (ref "IC1") (pin "25") (pinfunction "GPA4_25") (pintype "bidirectional"))
      (node (ref "IL5") (pin "A") (pinfunction "A_A") (pintype "passive"))
      (node (ref "IR2") (pin "4") (pinfunction "1_4") (pintype "passive"))
      (node (ref "OK2") (pin "15") (pinfunction "EMIT_15") (pintype "passive"))
    )
    (net (code "34") (name "GPA5") (class "Default")
      (node (ref "IC1") (pin "26") (pinfunction "GPA5_26") (pintype "bidirectional"))
      (node (ref "IL6") (pin "A") (pinfunction "A_A") (pintype "passive"))
      (node (ref "IR2") (pin "3") (pinfunction "1_3") (pintype "passive"))
      (node (ref "OK2") (pin "13") (pinfunction "EMIT_13") (pintype "passive"))
    )
    (net (code "35") (name "GPA6") (class "Default")
      (node (ref "IC1") (pin "27") (pinfunction "GPA6_27") (pintype "bidirectional"))
      (node (ref "IL7") (pin "A") (pinfunction "A_A") (pintype "passive"))
      (node (ref "IR2") (pin "2") (pinfunction "1_2") (pintype "passive"))
      (node (ref "OK2") (pin "11") (pinfunction "EMIT_11") (pintype "passive"))
    )
    (net (code "36") (name "GPA7") (class "Default")
      (node (ref "IC1") (pin "28") (pinfunction "GPA7_28") (pintype "bidirectional"))
      (node (ref "IL8") (pin "A") (pinfunction "A_A") (pintype "passive"))
      (node (ref "IR2") (pin "1") (pinfunction "1_1") (pintype "passive"))
      (node (ref "OK2") (pin "9") (pinfunction "EMIT_9") (pintype "passive"))
    )
    (net (code "37") (name "GPB0") (class "Default")
      (node (ref "IC1") (pin "1") (pinfunction "GPB0_1") (pintype "bidirectional"))
      (node (ref "OR4") (pin "8") (pinfunction "2_8") (pintype "passive"))
    )
    (net (code "38") (name "GPB1") (class "Default")
      (node (ref "IC1") (pin "2") (pinfunction "GPB1_2") (pintype "bidirectional"))
      (node (ref "OR4") (pin "7") (pinfunction "2_7") (pintype "passive"))
    )
    (net (code "39") (name "GPB2") (class "Default")
      (node (ref "IC1") (pin "3") (pinfunction "GPB2_3") (pintype "bidirectional"))
      (node (ref "OR4") (pin "6") (pinfunction "2_6") (pintype "passive"))
    )
    (net (code "40") (name "GPB3") (class "Default")
      (node (ref "IC1") (pin "4") (pinfunction "GPB3_4") (pintype "bidirectional"))
      (node (ref "OR4") (pin "5") (pinfunction "2_5") (pintype "passive"))
    )
    (net (code "41") (name "GPB4") (class "Default")
      (node (ref "IC1") (pin "5") (pinfunction "GPB4_5") (pintype "bidirectional"))
      (node (ref "OR1") (pin "8") (pinfunction "2_8") (pintype "passive"))
    )
    (net (code "42") (name "GPB5") (class "Default")
      (node (ref "IC1") (pin "6") (pinfunction "GPB5_6") (pintype "bidirectional"))
      (node (ref "OR1") (pin "7") (pinfunction "2_7") (pintype "passive"))
    )
    (net (code "43") (name "GPB6") (class "Default")
      (node (ref "IC1") (pin "7") (pinfunction "GPB6_7") (pintype "bidirectional"))
      (node (ref "OR1") (pin "6") (pinfunction "2_6") (pintype "passive"))
    )
    (net (code "44") (name "GPB7") (class "Default")
      (node (ref "IC1") (pin "8") (pinfunction "GPB7_8") (pintype "bidirectional"))
      (node (ref "OR1") (pin "5") (pinfunction "2_5") (pintype "passive"))
    )
    (net (code "45") (name "IO5") (class "Default")
      (node (ref "OK4") (pin "15") (pinfunction "EMIT_15") (pintype "passive"))
      (node (ref "OR6") (pin "8") (pinfunction "2_8") (pintype "passive"))
      (node (ref "U1") (pin "4") (pinfunction "4B_4") (pintype "input"))
    )
    (net (code "46") (name "IO6") (class "Default")
      (node (ref "OK4") (pin "13") (pinfunction "EMIT_13") (pintype "passive"))
      (node (ref "OR6") (pin "2") (pinfunction "1_2") (pintype "passive"))
      (node (ref "U1") (pin "3") (pinfunction "3B_3") (pintype "input"))
    )
    (net (code "47") (name "IO7") (class "Default")
      (node (ref "OK4") (pin "11") (pinfunction "EMIT_11") (pintype "passive"))
      (node (ref "OR6") (pin "3") (pinfunction "1_3") (pintype "passive"))
      (node (ref "U1") (pin "2") (pinfunction "2B_2") (pintype "input"))
    )
    (net (code "48") (name "IO8") (class "Default")
      (node (ref "OK4") (pin "9") (pinfunction "EMIT_9") (pintype "passive"))
      (node (ref "OR6") (pin "4") (pinfunction "1_4") (pintype "passive"))
      (node (ref "U1") (pin "1") (pinfunction "1B_1") (pintype "input"))
    )
    (net (code "49") (name "LEDA") (class "Default")
      (node (ref "ER3") (pin "1") (pinfunction "1_1") (pintype "passive"))
      (node (ref "U$2") (pin "Y+") (pinfunction "Y+_Y+") (pintype "bidirectional"))
    )
    (net (code "50") (name "LEDB") (class "Default")
      (node (ref "ER4") (pin "1") (pinfunction "1_1") (pintype "passive"))
      (node (ref "U$2") (pin "G+") (pinfunction "G+_G+") (pintype "bidirectional"))
    )
    (net (code "51") (name "Net-(ENC-LEDA)") (class "Default")
      (node (ref "ENC") (pin "27") (pinfunction "LEDA_27") (pintype "output"))
      (node (ref "ER3") (pin "2") (pinfunction "2_2") (pintype "passive"))
    )
    (net (code "52") (name "Net-(ENC-LEDB)") (class "Default")
      (node (ref "ENC") (pin "26") (pinfunction "LEDB_26") (pintype "output"))
      (node (ref "ER4") (pin "2") (pinfunction "2_2") (pintype "passive"))
    )
    (net (code "53") (name "Net-(ENC-OSC1)") (class "Default")
      (node (ref "EC1") (pin "1") (pinfunction "1_1") (pintype "passive"))
      (node (ref "ENC") (pin "23") (pinfunction "OSC1_23") (pintype "input"))
      (node (ref "Q2") (pin "2") (pinfunction "2_2") (pintype "passive"))
    )
    (net (code "54") (name "Net-(ENC-OSC2)") (class "Default")
      (node (ref "EC2") (pin "1") (pinfunction "1_1") (pintype "passive"))
      (node (ref "ENC") (pin "24") (pinfunction "OSC2_24") (pintype "output"))
      (node (ref "Q2") (pin "1") (pinfunction "1_1") (pintype "passive"))
    )
    (net (code "55") (name "Net-(ENC-RBIAS)") (class "Default")
      (node (ref "ENC") (pin "14") (pinfunction "RBIAS_14") (pintype "passive"))
      (node (ref "ER10") (pin "1") (pinfunction "1_1") (pintype "passive"))
    )
    (net (code "56") (name "Net-(ENC-RESET)") (class "Default")
      (node (ref "ENC") (pin "10") (pinfunction "RESET_10") (pintype "input"))
      (node (ref "ER1") (pin "1") (pinfunction "1_1") (pintype "passive"))
    )
    (net (code "57") (name "Net-(ENC-TPIN+)") (class "Default")
      (node (ref "ENC") (pin "13") (pinfunction "TPIN+_13") (pintype "input"))
      (node (ref "ERN1") (pin "6") (pinfunction "2_6") (pintype "passive"))
      (node (ref "U$2") (pin "RD+") (pinfunction "RD+_RD+") (pintype "bidirectional"))
    )
    (net (code "58") (name "Net-(ENC-TPIN-)") (class "Default")
      (node (ref "ENC") (pin "12") (pinfunction "TPIN-_12") (pintype "input"))
      (node (ref "ERN1") (pin "5") (pinfunction "2_5") (pintype "passive"))
      (node (ref "U$2") (pin "RD-") (pinfunction "RD-_RD-") (pintype "bidirectional"))
    )
    (net (code "59") (name "Net-(ENC-TPOUT+)") (class "Default")
      (node (ref "ENC") (pin "17") (pinfunction "TPOUT+_17") (pintype "output"))
      (node (ref "ERN1") (pin "1") (pinfunction "1_1") (pintype "passive"))
      (node (ref "U$2") (pin "TD+") (pinfunction "TD+_TD+") (pintype "bidirectional"))
    )
    (net (code "60") (name "Net-(ENC-TPOUT-)") (class "Default")
      (node (ref "ENC") (pin "16") (pinfunction "TPOUT-_16") (pintype "output"))
      (node (ref "ERN1") (pin "2") (pinfunction "1_2") (pintype "passive"))
      (node (ref "U$2") (pin "TD-") (pinfunction "TD-_TD-") (pintype "bidirectional"))
    )
    (net (code "61") (name "Net-(ENC-VCAP)") (class "Default")
      (node (ref "EC3") (pin "+") (pinfunction "+_+") (pintype "passive"))
      (node (ref "ENC") (pin "1") (pinfunction "VCAP_1") (pintype "power_in"))
    )
    (net (code "62") (name "Net-(ERN1A-2)") (class "Default")
      (node (ref "EC4") (pin "1") (pinfunction "1_1") (pintype "passive"))
      (node (ref "EL1") (pin "2") (pinfunction "2_2") (pintype "passive"))
      (node (ref "ERN1") (pin "7") (pinfunction "2_7") (pintype "passive"))
      (node (ref "ERN1") (pin "8") (pinfunction "2_8") (pintype "passive"))
      (node (ref "U$2") (pin "P4") (pinfunction "P4_P4") (pintype "bidirectional"))
    )
    (net (code "63") (name "Net-(ERN1C-1)") (class "Default")
      (node (ref "EC5") (pin "1") (pinfunction "1_1") (pintype "passive"))
      (node (ref "ERN1") (pin "3") (pinfunction "1_3") (pintype "passive"))
      (node (ref "ERN1") (pin "4") (pinfunction "1_4") (pintype "passive"))
      (node (ref "U$2") (pin "P5") (pinfunction "P5_P5") (pintype "bidirectional"))
    )
    (net (code "64") (name "Net-(IC1-A0)") (class "Default")
      (node (ref "IC1") (pin "15") (pinfunction "A0_15") (pintype "input"))
      (node (ref "MR3") (pin "1") (pinfunction "1_1") (pintype "passive"))
    )
    (net (code "65") (name "Net-(IIR1A-2)") (class "Default")
      (node (ref "IIR1") (pin "8") (pinfunction "2_8") (pintype "passive"))
      (node (ref "OK1") (pin "1") (pinfunction "A_1") (pintype "passive"))
    )
    (net (code "66") (name "Net-(IIR1B-1)") (class "Default")
      (node (ref "IIR1") (pin "2") (pinfunction "1_2") (pintype "passive"))
      (node (ref "XI1") (pin "3") (pinfunction "SK_3") (pintype "passive"))
    )
    (net (code "67") (name "Net-(IIR1B-2)") (class "Default")
      (node (ref "IIR1") (pin "7") (pinfunction "2_7") (pintype "passive"))
      (node (ref "OK1") (pin "3") (pinfunction "A_3") (pintype "passive"))
    )
    (net (code "68") (name "Net-(IIR1C-1)") (class "Default")
      (node (ref "IIR1") (pin "3") (pinfunction "1_3") (pintype "passive"))
      (node (ref "XI1") (pin "4") (pinfunction "SK_4") (pintype "passive"))
    )
    (net (code "69") (name "Net-(IIR1C-2)") (class "Default")
      (node (ref "IIR1") (pin "6") (pinfunction "2_6") (pintype "passive"))
      (node (ref "OK1") (pin "5") (pinfunction "A_5") (pintype "passive"))
    )
    (net (code "70") (name "Net-(IIR1D-1)") (class "Default")
      (node (ref "IIR1") (pin "4") (pinfunction "1_4") (pintype "passive"))
      (node (ref "XI1") (pin "5") (pinfunction "SK_5") (pintype "passive"))
    )
    (net (code "71") (name "Net-(IIR1D-2)") (class "Default")
      (node (ref "IIR1") (pin "5") (pinfunction "2_5") (pintype "passive"))
      (node (ref "OK1") (pin "7") (pinfunction "A_7") (pintype "passive"))
    )
    (net (code "72") (name "Net-(IIR2A-2)") (class "Default")
      (node (ref "IIR2") (pin "8") (pinfunction "2_8") (pintype "passive"))
      (node (ref "OK2") (pin "1") (pinfunction "A_1") (pintype "passive"))
    )
    (net (code "73") (name "Net-(IIR2B-1)") (class "Default")
      (node (ref "IIR2") (pin "2") (pinfunction "1_2") (pintype "passive"))
      (node (ref "XI2") (pin "3") (pinfunction "SK_3") (pintype "passive"))
    )
    (net (code "74") (name "Net-(IIR2B-2)") (class "Default")
      (node (ref "IIR2") (pin "7") (pinfunction "2_7") (pintype "passive"))
      (node (ref "OK2") (pin "3") (pinfunction "A_3") (pintype "passive"))
    )
    (net (code "75") (name "Net-(IIR2C-1)") (class "Default")
      (node (ref "IIR2") (pin "3") (pinfunction "1_3") (pintype "passive"))
      (node (ref "XI2") (pin "4") (pinfunction "SK_4") (pintype "passive"))
    )
    (net (code "76") (name "Net-(IIR2C-2)") (class "Default")
      (node (ref "IIR2") (pin "6") (pinfunction "2_6") (pintype "passive"))
      (node (ref "OK2") (pin "5") (pinfunction "A_5") (pintype "passive"))
    )
    (net (code "77") (name "Net-(IIR2D-1)") (class "Default")
      (node (ref "IIR2") (pin "4") (pinfunction "1_4") (pintype "passive"))
      (node (ref "XI2") (pin "5") (pinfunction "SK_5") (pintype "passive"))
    )
    (net (code "78") (name "Net-(IIR2D-2)") (class "Default")
      (node (ref "IIR2") (pin "5") (pinfunction "2_5") (pintype "passive"))
      (node (ref "OK2") (pin "7") (pinfunction "A_7") (pintype "passive"))
    )
    (net (code "79") (name "Net-(INDL-PadA)") (class "Default")
      (node (ref "INDL") (pin "A") (pinfunction "A_A") (pintype "passive"))
      (node (ref "R6") (pin "2") (pinfunction "2_2") (pintype "passive"))
    )
    (net (code "80") (name "Net-(IR3A-2)") (class "Default")
      (node (ref "IL1") (pin "C") (pinfunction "C_C") (pintype "passive"))
      (node (ref "IR3") (pin "8") (pinfunction "2_8") (pintype "passive"))
    )
    (net (code "81") (name "Net-(IR3B-2)") (class "Default")
      (node (ref "IL2") (pin "C") (pinfunction "C_C") (pintype "passive"))
      (node (ref "IR3") (pin "7") (pinfunction "2_7") (pintype "passive"))
    )
    (net (code "82") (name "Net-(IR3C-2)") (class "Default")
      (node (ref "IL3") (pin "C") (pinfunction "C_C") (pintype "passive"))
      (node (ref "IR3") (pin "6") (pinfunction "2_6") (pintype "passive"))
    )
    (net (code "83") (name "Net-(IR3D-2)") (class "Default")
      (node (ref "IL4") (pin "C") (pinfunction "C_C") (pintype "passive"))
      (node (ref "IR3") (pin "5") (pinfunction "2_5") (pintype "passive"))
    )
    (net (code "84") (name "Net-(IR4A-2)") (class "Default")
      (node (ref "IL5") (pin "C") (pinfunction "C_C") (pintype "passive"))
      (node (ref "IR4") (pin "8") (pinfunction "2_8") (pintype "passive"))
    )
    (net (code "85") (name "Net-(IR4B-2)") (class "Default")
      (node (ref "IL6") (pin "C") (pinfunction "C_C") (pintype "passive"))
      (node (ref "IR4") (pin "7") (pinfunction "2_7") (pintype "passive"))
    )
    (net (code "86") (name "Net-(IR4C-2)") (class "Default")
      (node (ref "IL7") (pin "C") (pinfunction "C_C") (pintype "passive"))
      (node (ref "IR4") (pin "6") (pinfunction "2_6") (pintype "passive"))
    )
    (net (code "87") (name "Net-(IR4D-2)") (class "Default")
      (node (ref "IL8") (pin "C") (pinfunction "C_C") (pintype "passive"))
      (node (ref "IR4") (pin "5") (pinfunction "2_5") (pintype "passive"))
    )
    (net (code "88") (name "Net-(MC-PB6(XTAL1{slash}TOSC1))") (class "Default")
      (node (ref "MC") (pin "7") (pinfunction "PB6(XTAL1/TOSC1)_7") (pintype "bidirectional"))
      (node (ref "Q1") (pin "1") (pinfunction "1_1") (pintype "passive"))
    )
    (net (code "89") (name "Net-(MC-PB7(XTAL2{slash}TOSC2))") (class "Default")
      (node (ref "MC") (pin "8") (pinfunction "PB7(XTAL2/TOSC2)_8") (pintype "bidirectional"))
      (node (ref "Q1") (pin "3") (pinfunction "3_3") (pintype "passive"))
    )
    (net (code "90") (name "Net-(OD1-PadC)") (class "Default")
      (node (ref "OD1") (pin "C") (pinfunction "C_C") (pintype "passive"))
      (node (ref "OMF") (pin "2") (pinfunction "2_2") (pintype "bidirectional"))
    )
    (net (code "91") (name "Net-(OK3A-A)") (class "Default")
      (node (ref "OK3") (pin "1") (pinfunction "A_1") (pintype "passive"))
      (node (ref "OR1") (pin "4") (pinfunction "1_4") (pintype "passive"))
    )
    (net (code "92") (name "Net-(OK3A-C)") (class "Default")
      (node (ref "OK3") (pin "2") (pinfunction "C_2") (pintype "passive"))
      (node (ref "OL1") (pin "A") (pinfunction "A_A") (pintype "passive"))
    )
    (net (code "93") (name "Net-(OK3A-COL)") (class "Default")
      (node (ref "OK3") (pin "16") (pinfunction "COL_16") (pintype "passive"))
      (node (ref "OR3") (pin "1") (pinfunction "1_1") (pintype "passive"))
    )
    (net (code "94") (name "Net-(OK3B-A)") (class "Default")
      (node (ref "OK3") (pin "3") (pinfunction "A_3") (pintype "passive"))
      (node (ref "OR1") (pin "3") (pinfunction "1_3") (pintype "passive"))
    )
    (net (code "95") (name "Net-(OK3B-C)") (class "Default")
      (node (ref "OK3") (pin "4") (pinfunction "C_4") (pintype "passive"))
      (node (ref "OL2") (pin "A") (pinfunction "A_A") (pintype "passive"))
    )
    (net (code "96") (name "Net-(OK3B-COL)") (class "Default")
      (node (ref "OK3") (pin "14") (pinfunction "COL_14") (pintype "passive"))
      (node (ref "OR3") (pin "2") (pinfunction "1_2") (pintype "passive"))
    )
    (net (code "97") (name "Net-(OK3C-A)") (class "Default")
      (node (ref "OK3") (pin "5") (pinfunction "A_5") (pintype "passive"))
      (node (ref "OR1") (pin "2") (pinfunction "1_2") (pintype "passive"))
    )
    (net (code "98") (name "Net-(OK3C-C)") (class "Default")
      (node (ref "OK3") (pin "6") (pinfunction "C_6") (pintype "passive"))
      (node (ref "OL3") (pin "A") (pinfunction "A_A") (pintype "passive"))
    )
    (net (code "99") (name "Net-(OK3C-COL)") (class "Default")
      (node (ref "OK3") (pin "12") (pinfunction "COL_12") (pintype "passive"))
      (node (ref "OR3") (pin "3") (pinfunction "1_3") (pintype "passive"))
    )
    (net (code "100") (name "Net-(OK3D-A)") (class "Default")
      (node (ref "OK3") (pin "7") (pinfunction "A_7") (pintype "passive"))
      (node (ref "OR1") (pin "1") (pinfunction "1_1") (pintype "passive"))
    )
    (net (code "101") (name "Net-(OK3D-C)") (class "Default")
      (node (ref "OK3") (pin "8") (pinfunction "C_8") (pintype "passive"))
      (node (ref "OL4") (pin "A") (pinfunction "A_A") (pintype "passive"))
    )
    (net (code "102") (name "Net-(OK3D-COL)") (class "Default")
      (node (ref "OK3") (pin "10") (pinfunction "COL_10") (pintype "passive"))
      (node (ref "OR3") (pin "4") (pinfunction "1_4") (pintype "passive"))
    )
    (net (code "103") (name "Net-(OK4A-A)") (class "Default")
      (node (ref "OK4") (pin "1") (pinfunction "A_1") (pintype "passive"))
      (node (ref "OR4") (pin "4") (pinfunction "1_4") (pintype "passive"))
    )
    (net (code "104") (name "Net-(OK4A-C)") (class "Default")
      (node (ref "OK4") (pin "2") (pinfunction "C_2") (pintype "passive"))
      (node (ref "OL5") (pin "A") (pinfunction "A_A") (pintype "passive"))
    )
    (net (code "105") (name "Net-(OK4A-COL)") (class "Default")
      (node (ref "OK4") (pin "16") (pinfunction "COL_16") (pintype "passive"))
      (node (ref "OR5") (pin "1") (pinfunction "1_1") (pintype "passive"))
    )
    (net (code "106") (name "Net-(OK4B-A)") (class "Default")
      (node (ref "OK4") (pin "3") (pinfunction "A_3") (pintype "passive"))
      (node (ref "OR4") (pin "3") (pinfunction "1_3") (pintype "passive"))
    )
    (net (code "107") (name "Net-(OK4B-C)") (class "Default")
      (node (ref "OK4") (pin "4") (pinfunction "C_4") (pintype "passive"))
      (node (ref "OL6") (pin "A") (pinfunction "A_A") (pintype "passive"))
    )
    (net (code "108") (name "Net-(OK4B-COL)") (class "Default")
      (node (ref "OK4") (pin "14") (pinfunction "COL_14") (pintype "passive"))
      (node (ref "OR5") (pin "2") (pinfunction "1_2") (pintype "passive"))
    )
    (net (code "109") (name "Net-(OK4C-A)") (class "Default")
      (node (ref "OK4") (pin "5") (pinfunction "A_5") (pintype "passive"))
      (node (ref "OR4") (pin "2") (pinfunction "1_2") (pintype "passive"))
    )
    (net (code "110") (name "Net-(OK4C-C)") (class "Default")
      (node (ref "OK4") (pin "6") (pinfunction "C_6") (pintype "passive"))
      (node (ref "OL7") (pin "A") (pinfunction "A_A") (pintype "passive"))
    )
    (net (code "111") (name "Net-(OK4C-COL)") (class "Default")
      (node (ref "OK4") (pin "12") (pinfunction "COL_12") (pintype "passive"))
      (node (ref "OR5") (pin "3") (pinfunction "1_3") (pintype "passive"))
    )
    (net (code "112") (name "Net-(OK4D-A)") (class "Default")
      (node (ref "OK4") (pin "7") (pinfunction "A_7") (pintype "passive"))
      (node (ref "OR4") (pin "1") (pinfunction "1_1") (pintype "passive"))
    )
    (net (code "113") (name "Net-(OK4D-C)") (class "Default")
      (node (ref "OK4") (pin "8") (pinfunction "C_8") (pintype "passive"))
      (node (ref "OL8") (pin "A") (pinfunction "A_A") (pintype "passive"))
    )
    (net (code "114") (name "Net-(OK4D-COL)") (class "Default")
      (node (ref "OK4") (pin "10") (pinfunction "COL_10") (pintype "passive"))
      (node (ref "OR5") (pin "4") (pinfunction "1_4") (pintype "passive"))
    )
    (net (code "115") (name "Net-(PD1-PadC)") (class "Default")
      (node (ref "PD1") (pin "C") (pinfunction "C_C") (pintype "passive"))
      (node (ref "PF1") (pin "1") (pinfunction "1_1") (pintype "passive"))
    )
    (net (code "116") (name "Net-(PIC33-OUT)") (class "Default")
      (node (ref "PCO") (pin "P$2") (pinfunction "P$2_P$2") (pintype "passive"))
      (node (ref "PD2") (pin "C") (pinfunction "C_C") (pintype "passive"))
      (node (ref "PIC33") (pin "2") (pinfunction "OUT_2") (pintype "output"))
    )
    (net (code "117") (name "Net-(PL-PadA)") (class "Default")
      (node (ref "PL") (pin "A") (pinfunction "A_A") (pintype "passive"))
      (node (ref "PR1") (pin "1") (pinfunction "1_1") (pintype "passive"))
    )
    (net (code "118") (name "Net-(U1-1C)") (class "Default")
      (node (ref "D1") (pin "2") (pinfunction "2_2") (pintype "bidirectional"))
      (node (ref "OF8") (pin "2") (pinfunction "2_2") (pintype "bidirectional"))
      (node (ref "U1") (pin "18") (pinfunction "1C_18") (pintype "output"))
    )
    (net (code "119") (name "Net-(U1-2C)") (class "Default")
      (node (ref "D1") (pin "1") (pinfunction "1_1") (pintype "bidirectional"))
      (node (ref "OF7") (pin "2") (pinfunction "2_2") (pintype "bidirectional"))
      (node (ref "U1") (pin "17") (pinfunction "2C_17") (pintype "output"))
    )
    (net (code "120") (name "Net-(U1-3C)") (class "Default")
      (node (ref "D2") (pin "2") (pinfunction "2_2") (pintype "bidirectional"))
      (node (ref "OF6") (pin "2") (pinfunction "2_2") (pintype "bidirectional"))
      (node (ref "U1") (pin "16") (pinfunction "3C_16") (pintype "output"))
    )
    (net (code "121") (name "Net-(U1-4C)") (class "Default")
      (node (ref "D2") (pin "1") (pinfunction "1_1") (pintype "bidirectional"))
      (node (ref "OF5") (pin "2") (pinfunction "2_2") (pintype "bidirectional"))
      (node (ref "U1") (pin "15") (pinfunction "4C_15") (pintype "output"))
    )
    (net (code "122") (name "Net-(U1-5C)") (class "Default")
      (node (ref "D3") (pin "2") (pinfunction "2_2") (pintype "bidirectional"))
      (node (ref "OF4") (pin "2") (pinfunction "2_2") (pintype "bidirectional"))
      (node (ref "U1") (pin "14") (pinfunction "5C_14") (pintype "output"))
    )
    (net (code "123") (name "Net-(U1-6C)") (class "Default")
      (node (ref "D3") (pin "1") (pinfunction "1_1") (pintype "bidirectional"))
      (node (ref "OF3") (pin "2") (pinfunction "2_2") (pintype "bidirectional"))
      (node (ref "U1") (pin "13") (pinfunction "6C_13") (pintype "output"))
    )
    (net (code "124") (name "Net-(U1-7C)") (class "Default")
      (node (ref "D4") (pin "2") (pinfunction "2_2") (pintype "bidirectional"))
      (node (ref "OF2") (pin "2") (pinfunction "2_2") (pintype "bidirectional"))
      (node (ref "U1") (pin "12") (pinfunction "7C_12") (pintype "output"))
    )
    (net (code "125") (name "Net-(U1-8C)") (class "Default")
      (node (ref "D4") (pin "1") (pinfunction "1_1") (pintype "bidirectional"))
      (node (ref "OF1") (pin "2") (pinfunction "2_2") (pintype "bidirectional"))
      (node (ref "U1") (pin "11") (pinfunction "8C_11") (pintype "output"))
    )
    (net (code "126") (name "Net-(XI1B-SK)") (class "Default")
      (node (ref "IIR1") (pin "1") (pinfunction "1_1") (pintype "passive"))
      (node (ref "XI1") (pin "2") (pinfunction "SK_2") (pintype "passive"))
    )
    (net (code "127") (name "Net-(XI2B-SK)") (class "Default")
      (node (ref "IIR2") (pin "1") (pinfunction "1_1") (pintype "passive"))
      (node (ref "XI2") (pin "2") (pinfunction "SK_2") (pintype "passive"))
    )
    (net (code "128") (name "Net-(XOA-SK)") (class "Default")
      (node (ref "OD1") (pin "A") (pinfunction "A_A") (pintype "passive"))
      (node (ref "XO") (pin "1") (pinfunction "SK_1") (pintype "passive"))
    )
    (net (code "129") (name "Net-(XOB-SK)") (class "Default")
      (node (ref "OF8") (pin "1") (pinfunction "1_1") (pintype "bidirectional"))
      (node (ref "XO") (pin "10") (pinfunction "SK_10") (pintype "passive"))
    )
    (net (code "130") (name "Net-(XOD-SK)") (class "Default")
      (node (ref "OF1") (pin "1") (pinfunction "1_1") (pintype "bidirectional"))
      (node (ref "XO") (pin "3") (pinfunction "SK_3") (pintype "passive"))
    )
    (net (code "131") (name "Net-(XOE-SK)") (class "Default")
      (node (ref "OF2") (pin "1") (pinfunction "1_1") (pintype "bidirectional"))
      (node (ref "XO") (pin "4") (pinfunction "SK_4") (pintype "passive"))
    )
    (net (code "132") (name "Net-(XOF-SK)") (class "Default")
      (node (ref "OF3") (pin "1") (pinfunction "1_1") (pintype "bidirectional"))
      (node (ref "XO") (pin "5") (pinfunction "SK_5") (pintype "passive"))
    )
    (net (code "133") (name "Net-(XOG-SK)") (class "Default")
      (node (ref "OF4") (pin "1") (pinfunction "1_1") (pintype "bidirectional"))
      (node (ref "XO") (pin "6") (pinfunction "SK_6") (pintype "passive"))
    )
    (net (code "134") (name "Net-(XOH-SK)") (class "Default")
      (node (ref "OF5") (pin "1") (pinfunction "1_1") (pintype "bidirectional"))
      (node (ref "XO") (pin "7") (pinfunction "SK_7") (pintype "passive"))
    )
    (net (code "135") (name "Net-(XOI-SK)") (class "Default")
      (node (ref "OF6") (pin "1") (pinfunction "1_1") (pintype "bidirectional"))
      (node (ref "XO") (pin "8") (pinfunction "SK_8") (pintype "passive"))
    )
    (net (code "136") (name "Net-(XOJ-SK)") (class "Default")
      (node (ref "OF7") (pin "1") (pinfunction "1_1") (pintype "bidirectional"))
      (node (ref "XO") (pin "9") (pinfunction "SK_9") (pintype "passive"))
    )
    (net (code "137") (name "OI1") (class "Default")
      (node (ref "OK3") (pin "15") (pinfunction "EMIT_15") (pintype "passive"))
      (node (ref "OR2") (pin "1") (pinfunction "1_1") (pintype "passive"))
      (node (ref "U1") (pin "8") (pinfunction "8B_8") (pintype "input"))
    )
    (net (code "138") (name "OI2") (class "Default")
      (node (ref "OK3") (pin "13") (pinfunction "EMIT_13") (pintype "passive"))
      (node (ref "OR2") (pin "2") (pinfunction "1_2") (pintype "passive"))
      (node (ref "U1") (pin "7") (pinfunction "7B_7") (pintype "input"))
    )
    (net (code "139") (name "OI3") (class "Default")
      (node (ref "OK3") (pin "11") (pinfunction "EMIT_11") (pintype "passive"))
      (node (ref "OR2") (pin "3") (pinfunction "1_3") (pintype "passive"))
      (node (ref "U1") (pin "6") (pinfunction "6B_6") (pintype "input"))
    )
    (net (code "140") (name "OI4") (class "Default")
      (node (ref "OK3") (pin "9") (pinfunction "EMIT_9") (pintype "passive"))
      (node (ref "OR2") (pin "4") (pinfunction "1_4") (pintype "passive"))
      (node (ref "U1") (pin "5") (pinfunction "5B_5") (pintype "input"))
    )
    (net (code "141") (name "RAW_IV") (class "Default")
      (node (ref "GPIO") (pin "1") (pinfunction "S_1") (pintype "passive"))
      (node (ref "PC1") (pin "+") (pinfunction "+_+") (pintype "passive"))
      (node (ref "PF1") (pin "2") (pinfunction "2_2") (pintype "passive"))
      (node (ref "PIC33") (pin "1") (pinfunction "VIN_1") (pintype "input"))
    )
    (net (code "142") (name "RESET") (class "Default")
      (node (ref "BL") (pin "5") (pinfunction "S_5") (pintype "passive"))
      (node (ref "C2") (pin "1") (pinfunction "1_1") (pintype "passive"))
      (node (ref "MC") (pin "29") (pinfunction "PC6(/RESET)_29") (pintype "bidirectional"))
      (node (ref "R2") (pin "1") (pinfunction "1_1") (pintype "passive"))
      (node (ref "SR") (pin "1") (pinfunction "P_1") (pintype "passive"))
    )
    (net (code "143") (name "RXI") (class "Default")
      (node (ref "MC") (pin "30") (pinfunction "PD0(RXD)_30") (pintype "bidirectional"))
      (node (ref "PP") (pin "4") (pinfunction "S_4") (pintype "passive"))
    )
    (net (code "144") (name "TXO") (class "Default")
      (node (ref "MC") (pin "31") (pinfunction "PD1(TXD)_31") (pintype "bidirectional"))
      (node (ref "PP") (pin "3") (pinfunction "S_3") (pintype "passive"))
    )
    (net (code "145") (name "VDDO") (class "Default")
      (node (ref "D1") (pin "3") (pinfunction "3_3") (pintype "bidirectional"))
      (node (ref "D2") (pin "3") (pinfunction "3_3") (pintype "bidirectional"))
      (node (ref "D3") (pin "3") (pinfunction "3_3") (pintype "bidirectional"))
      (node (ref "D4") (pin "3") (pinfunction "3_3") (pintype "bidirectional"))
      (node (ref "EC6") (pin "+") (pinfunction "+_+") (pintype "passive"))
      (node (ref "OD2") (pin "C") (pinfunction "C_C") (pintype "passive"))
      (node (ref "OMF") (pin "1") (pinfunction "1_1") (pintype "bidirectional"))
      (node (ref "OR3") (pin "5") (pinfunction "2_5") (pintype "passive"))
      (node (ref "OR3") (pin "6") (pinfunction "2_6") (pintype "passive"))
      (node (ref "OR3") (pin "7") (pinfunction "2_7") (pintype "passive"))
      (node (ref "OR3") (pin "8") (pinfunction "2_8") (pintype "passive"))
      (node (ref "OR5") (pin "5") (pinfunction "2_5") (pintype "passive"))
      (node (ref "OR5") (pin "6") (pinfunction "2_6") (pintype "passive"))
      (node (ref "OR5") (pin "7") (pinfunction "2_7") (pintype "passive"))
      (node (ref "OR5") (pin "8") (pinfunction "2_8") (pintype "passive"))
      (node (ref "U1") (pin "10") (pinfunction "COM_10") (pintype "output"))
    )
    (net (code "146") (name "VIN") (class "Default")
      (node (ref "PD1") (pin "A") (pinfunction "A_A") (pintype "passive"))
      (node (ref "PJ1") (pin "VIN0") (pinfunction "PWR_VIN0") (pintype "bidirectional"))
      (node (ref "XV") (pin "2") (pinfunction "SK_2") (pintype "passive"))
    )
    (net (code "147") (name "WFGPIO0") (class "Default")
      (node (ref "GPIO") (pin "13") (pinfunction "S_13") (pintype "passive"))
      (node (ref "WIFI") (pin "GPIO0") (pinfunction "GPIO0_GPIO0") (pintype "bidirectional"))
    )
    (net (code "148") (name "WFGPIO2") (class "Default")
      (node (ref "GPIO") (pin "14") (pinfunction "S_14") (pintype "passive"))
      (node (ref "WIFI") (pin "GPIO2") (pinfunction "GPIO2_GPIO2") (pintype "bidirectional"))
    )
    (net (code "149") (name "unconnected-(ENC-CLKOUT-Pad3)") (class "Default")
      (node (ref "ENC") (pin "3") (pinfunction "CLKOUT_3") (pintype "output"))
    )
    (net (code "150") (name "unconnected-(ENC-WOL-Pad5)") (class "Default")
      (node (ref "ENC") (pin "5") (pinfunction "WOL_5") (pintype "output"))
    )
    (net (code "151") (name "unconnected-(IC1-INTA-Pad20)") (class "Default")
      (node (ref "IC1") (pin "20") (pinfunction "INTA_20") (pintype "output"))
    )
    (net (code "152") (name "unconnected-(PJ1-GND-PadP$4)") (class "Default")
      (node (ref "PJ1") (pin "P$4") (pinfunction "GND_P$4") (pintype "bidirectional"))
    )
    (net (code "153") (name "unconnected-(U$2-PadNC)") (class "Default")
      (node (ref "U$2") (pin "NC") (pinfunction "NC_NC") (pintype "bidirectional"))
    )
    (net (code "154") (name "unconnected-(WIFI-PadRST)") (class "Default")
      (node (ref "WIFI") (pin "RST") (pinfunction "RST_RST") (pintype "bidirectional"))
    )
  )
)
